# Main.net
KiCad netlist of a schematic drawn in Altium Designer
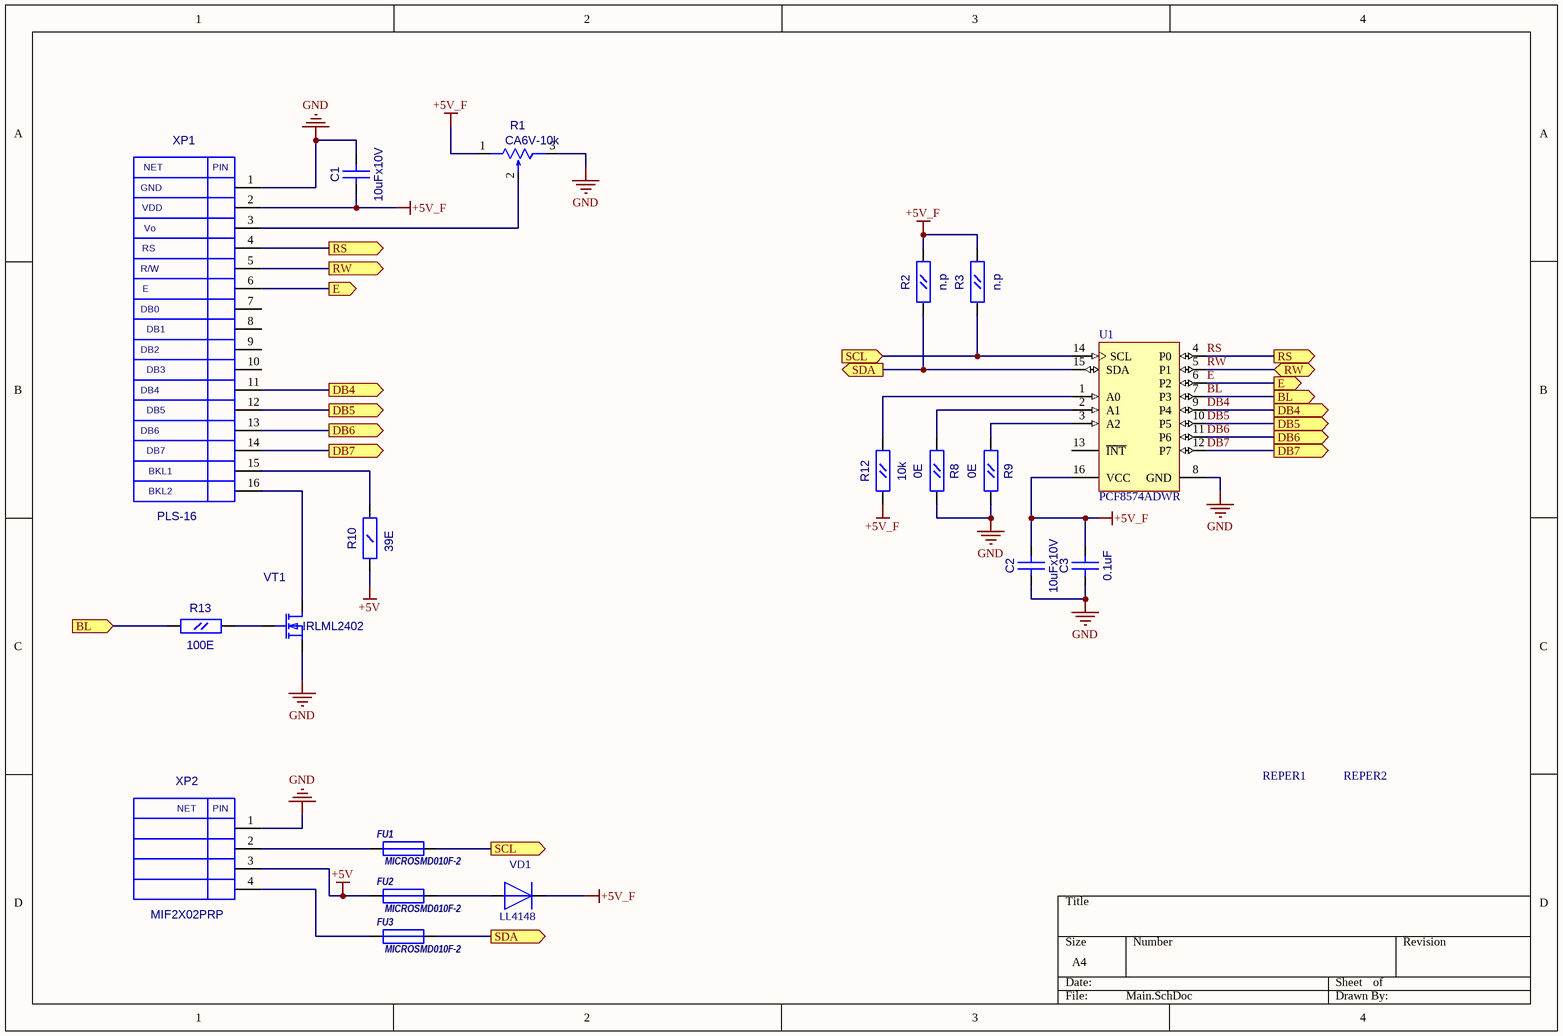
[diagram p0: Main.SchDoc]

(export (version "E")
  (design (tool "Eeschema 10.0.6"))
  (components
    (comp (ref "C1")
      (value "10uFx10V")
      (footprint "CC0805")
      (description "CC0805")
      (libsource (lib "gprs_modem_2") (part "CC0805"))
    )
    (comp (ref "C2")
      (value "10uFx10V")
      (footprint "CC0805")
      (description "CC0805")
      (libsource (lib "gprs_modem_2") (part "CC0805"))
    )
    (comp (ref "C3")
      (value "0.1uF")
      (footprint "CC0603")
      (description "CC0603")
      (libsource (lib "gprs_modem_2") (part "CC0603"))
    )
    (comp (ref "FU1")
      (value "MICROSMD010F-2")
      (footprint "RC1210")
      (description "MICROSMD")
      (libsource (lib "gprs_modem_2") (part "MICROSMD"))
    )
    (comp (ref "FU2")
      (value "MICROSMD010F-2")
      (footprint "RC1210")
      (description "MICROSMD")
      (libsource (lib "gprs_modem_2") (part "MICROSMD"))
    )
    (comp (ref "FU3")
      (value "MICROSMD010F-2")
      (footprint "RC1210")
      (description "MICROSMD")
      (libsource (lib "gprs_modem_2") (part "MICROSMD"))
    )
    (comp (ref "R1")
      (value "CA6V-10k")
      (footprint "3318P-1")
      (description "EVND8AA03B25")
      (libsource (lib "Schetchik") (part "3318P-1"))
    )
    (comp (ref "R2")
      (value "n.p")
      (footprint "RC0603")
      (description "RC0603")
      (libsource (lib "gprs_modem_2") (part "RC0603"))
    )
    (comp (ref "R3")
      (value "n.p")
      (footprint "RC0603")
      (description "RC0603")
      (libsource (lib "gprs_modem_2") (part "RC0603"))
    )
    (comp (ref "R8")
      (value "0E")
      (footprint "RC0603")
      (description "RC0603")
      (libsource (lib "gprs_modem_2") (part "RC0603"))
    )
    (comp (ref "R9")
      (value "0E")
      (footprint "RC0603")
      (description "RC0603")
      (libsource (lib "gprs_modem_2") (part "RC0603"))
    )
    (comp (ref "R10")
      (value "39E")
      (footprint "RC1206")
      (description "RC1206")
      (libsource (lib "gprs_modem_2") (part "RC1206"))
    )
    (comp (ref "R12")
      (value "10k")
      (footprint "RC0603")
      (description "RC0603")
      (libsource (lib "gprs_modem_2") (part "RC0603"))
    )
    (comp (ref "R13")
      (value "100E")
      (footprint "RC0603")
      (description "RC0603")
      (libsource (lib "gprs_modem_2") (part "RC0603"))
    )
    (comp (ref "REPER1")
      (value "REPER1.2")
      (footprint "REPER1.2")
      (libsource (lib "gprs_modem_2") (part "REPER1.2"))
    )
    (comp (ref "REPER2")
      (value "REPER1.2")
      (footprint "REPER1.2")
      (libsource (lib "gprs_modem_2") (part "REPER1.2"))
    )
    (comp (ref "U1")
      (value "PCF8574ADWR")
      (footprint "DW16_N")
      (fields (field (name "MANUFACTURER") "Texas Instruments"))
      (libsource (lib "Texas Instruments Interface I2C") (part "PCF8574ADWR"))
    )
    (comp (ref "VD1") (value "LL4148") (footprint "SOD-80") (libsource (lib "gprs_modem_2") (part "LL4148")))
    (comp (ref "VT1")
      (value "IRLML2402")
      (footprint "SOT-23(123)")
      (description "N-Channel Enhancement Mode Vertical DMOS FET")
      (libsource (lib "gprs_modem_2") (part "IRLML2402"))
    )
    (comp (ref "XP1") (value "PLS-16") (footprint "PIN16S") (libsource (lib "Schetchik") (part "PLS-16")))
    (comp (ref "XP2")
      (value "MIF2X02PRP")
      (footprint "MIF2X02PRP")
      (libsource (lib "gprs_modem_2") (part "MIF2X02PRP"))
    )
  )
  (nets
    (net (code "1") (name "+5V") (class "Default")
      (node (ref "FU2") (pin "1") (pintype "passive"))
      (node (ref "R10") (pin "1") (pinfunction "A_1") (pintype "passive"))
      (node (ref "XP2") (pin "3") (pinfunction "3_3") (pintype "passive"))
    )
    (net (code "2") (name "+5V_F") (class "Default")
      (node (ref "C1") (pin "1") (pinfunction "A_1") (pintype "passive"))
      (node (ref "C2") (pin "2") (pinfunction "B_2") (pintype "passive"))
      (node (ref "C3") (pin "2") (pinfunction "B_2") (pintype "passive"))
      (node (ref "R1") (pin "1") (pintype "passive"))
      (node (ref "R12") (pin "1") (pinfunction "A_1") (pintype "passive"))
      (node (ref "R2") (pin "2") (pinfunction "B_2") (pintype "passive"))
      (node (ref "R3") (pin "2") (pinfunction "B_2") (pintype "passive"))
      (node (ref "U1") (pin "16") (pinfunction "VCC_16") (pintype "power_in"))
      (node (ref "VD1") (pin "2") (pinfunction "+_2") (pintype "passive"))
      (node (ref "XP1") (pin "2") (pinfunction "2_2") (pintype "passive"))
    )
    (net (code "3") (name "/BL") (class "Default")
      (node (ref "R13") (pin "1") (pinfunction "A_1") (pintype "passive"))
      (node (ref "U1") (pin "7") (pinfunction "P3_7") (pintype "bidirectional"))
    )
    (net (code "4") (name "/DB4") (class "Default")
      (node (ref "U1") (pin "9") (pinfunction "P4_9") (pintype "bidirectional"))
      (node (ref "XP1") (pin "11") (pinfunction "11_11") (pintype "passive"))
    )
    (net (code "5") (name "/DB5") (class "Default")
      (node (ref "U1") (pin "10") (pinfunction "P5_10") (pintype "bidirectional"))
      (node (ref "XP1") (pin "12") (pinfunction "12_12") (pintype "passive"))
    )
    (net (code "6") (name "/DB6") (class "Default")
      (node (ref "U1") (pin "11") (pinfunction "P6_11") (pintype "bidirectional"))
      (node (ref "XP1") (pin "13") (pinfunction "13_13") (pintype "passive"))
    )
    (net (code "7") (name "/DB7") (class "Default")
      (node (ref "U1") (pin "12") (pinfunction "P7_12") (pintype "bidirectional"))
      (node (ref "XP1") (pin "14") (pinfunction "14_14") (pintype "passive"))
    )
    (net (code "8") (name "/E") (class "Default")
      (node (ref "U1") (pin "6") (pinfunction "P2_6") (pintype "bidirectional"))
      (node (ref "XP1") (pin "6") (pinfunction "6_6") (pintype "passive"))
    )
    (net (code "9") (name "/RS") (class "Default")
      (node (ref "U1") (pin "4") (pinfunction "P0_4") (pintype "bidirectional"))
      (node (ref "XP1") (pin "4") (pinfunction "4_4") (pintype "passive"))
    )
    (net (code "10") (name "/RW") (class "Default")
      (node (ref "U1") (pin "5") (pinfunction "P1_5") (pintype "bidirectional"))
      (node (ref "XP1") (pin "5") (pinfunction "5_5") (pintype "passive"))
    )
    (net (code "11") (name "/SCL") (class "Default")
      (node (ref "FU1") (pin "2") (pintype "passive"))
      (node (ref "R3") (pin "1") (pinfunction "A_1") (pintype "passive"))
      (node (ref "U1") (pin "14") (pinfunction "SCL_14") (pintype "input"))
    )
    (net (code "12") (name "/SDA") (class "Default")
      (node (ref "FU3") (pin "2") (pintype "passive"))
      (node (ref "R2") (pin "1") (pinfunction "A_1") (pintype "passive"))
      (node (ref "U1") (pin "15") (pinfunction "SDA_15") (pintype "bidirectional"))
    )
    (net (code "13") (name "GND") (class "Default")
      (node (ref "C1") (pin "2") (pinfunction "B_2") (pintype "passive"))
      (node (ref "C2") (pin "1") (pinfunction "A_1") (pintype "passive"))
      (node (ref "C3") (pin "1") (pinfunction "A_1") (pintype "passive"))
      (node (ref "R1") (pin "3") (pintype "passive"))
      (node (ref "R8") (pin "2") (pinfunction "B_2") (pintype "passive"))
      (node (ref "R9") (pin "2") (pinfunction "B_2") (pintype "passive"))
      (node (ref "U1") (pin "8") (pinfunction "GND_8") (pintype "power_in"))
      (node (ref "VT1") (pin "2") (pinfunction "S_2") (pintype "passive"))
      (node (ref "XP1") (pin "1") (pinfunction "1_1") (pintype "passive"))
      (node (ref "XP2") (pin "1") (pinfunction "1_1") (pintype "passive"))
    )
    (net (code "14") (name "Net-(FU1-Pad1)") (class "Default")
      (node (ref "FU1") (pin "1") (pintype "passive"))
      (node (ref "XP2") (pin "2") (pinfunction "2_2") (pintype "passive"))
    )
    (net (code "15") (name "Net-(FU3-Pad1)") (class "Default")
      (node (ref "FU3") (pin "1") (pintype "passive"))
      (node (ref "XP2") (pin "4") (pinfunction "4_4") (pintype "passive"))
    )
    (net (code "16") (name "Net-(R1-Pad2)") (class "Default")
      (node (ref "R1") (pin "2") (pintype "passive"))
      (node (ref "XP1") (pin "3") (pinfunction "3_3") (pintype "passive"))
    )
    (net (code "17") (name "Net-(R8-A)") (class "Default")
      (node (ref "R8") (pin "1") (pinfunction "A_1") (pintype "passive"))
      (node (ref "U1") (pin "2") (pinfunction "A1_2") (pintype "input"))
    )
    (net (code "18") (name "Net-(R9-A)") (class "Default")
      (node (ref "R9") (pin "1") (pinfunction "A_1") (pintype "passive"))
      (node (ref "U1") (pin "3") (pinfunction "A2_3") (pintype "input"))
    )
    (net (code "19") (name "Net-(R10-B)") (class "Default")
      (node (ref "R10") (pin "2") (pinfunction "B_2") (pintype "passive"))
      (node (ref "XP1") (pin "15") (pinfunction "15_15") (pintype "passive"))
    )
    (net (code "20") (name "Net-(R12-B)") (class "Default")
      (node (ref "R12") (pin "2") (pinfunction "B_2") (pintype "passive"))
      (node (ref "U1") (pin "1") (pinfunction "A0_1") (pintype "input"))
    )
    (net (code "21") (name "Net-(R13-B)") (class "Default")
      (node (ref "R13") (pin "2") (pinfunction "B_2") (pintype "passive"))
      (node (ref "VT1") (pin "1") (pinfunction "G_1") (pintype "passive"))
    )
    (net (code "22") (name "Net-(VD1--)") (class "Default")
      (node (ref "FU2") (pin "2") (pintype "passive"))
      (node (ref "VD1") (pin "1") (pinfunction "-_1") (pintype "passive"))
    )
    (net (code "23") (name "Net-(VT1-D)") (class "Default")
      (node (ref "VT1") (pin "3") (pinfunction "D_3") (pintype "passive"))
      (node (ref "XP1") (pin "16") (pinfunction "16_16") (pintype "passive"))
    )
    (net (code "24") (name "unconnected-(REPER1-Pad1)") (class "Default")
      (node (ref "REPER1") (pin "1") (pintype "passive"))
    )
    (net (code "25") (name "unconnected-(REPER2-Pad1)") (class "Default")
      (node (ref "REPER2") (pin "1") (pintype "passive"))
    )
    (net (code "26") (name "unconnected-(U1-~{INT}-Pad13)") (class "Default")
      (node (ref "U1") (pin "13") (pinfunction "~{INT}_13") (pintype "open_collector"))
    )
    (net (code "27") (name "unconnected-(XP1-Pad7)") (class "Default")
      (node (ref "XP1") (pin "7") (pinfunction "7_7") (pintype "passive"))
    )
    (net (code "28") (name "unconnected-(XP1-Pad8)") (class "Default")
      (node (ref "XP1") (pin "8") (pinfunction "8_8") (pintype "passive"))
    )
    (net (code "29") (name "unconnected-(XP1-Pad9)") (class "Default")
      (node (ref "XP1") (pin "9") (pinfunction "9_9") (pintype "passive"))
    )
    (net (code "30") (name "unconnected-(XP1-Pad10)") (class "Default")
      (node (ref "XP1") (pin "10") (pinfunction "10_10") (pintype "passive"))
    )
  )
)
